# 1.net
KiCad netlist of a schematic drawn in EAGLE
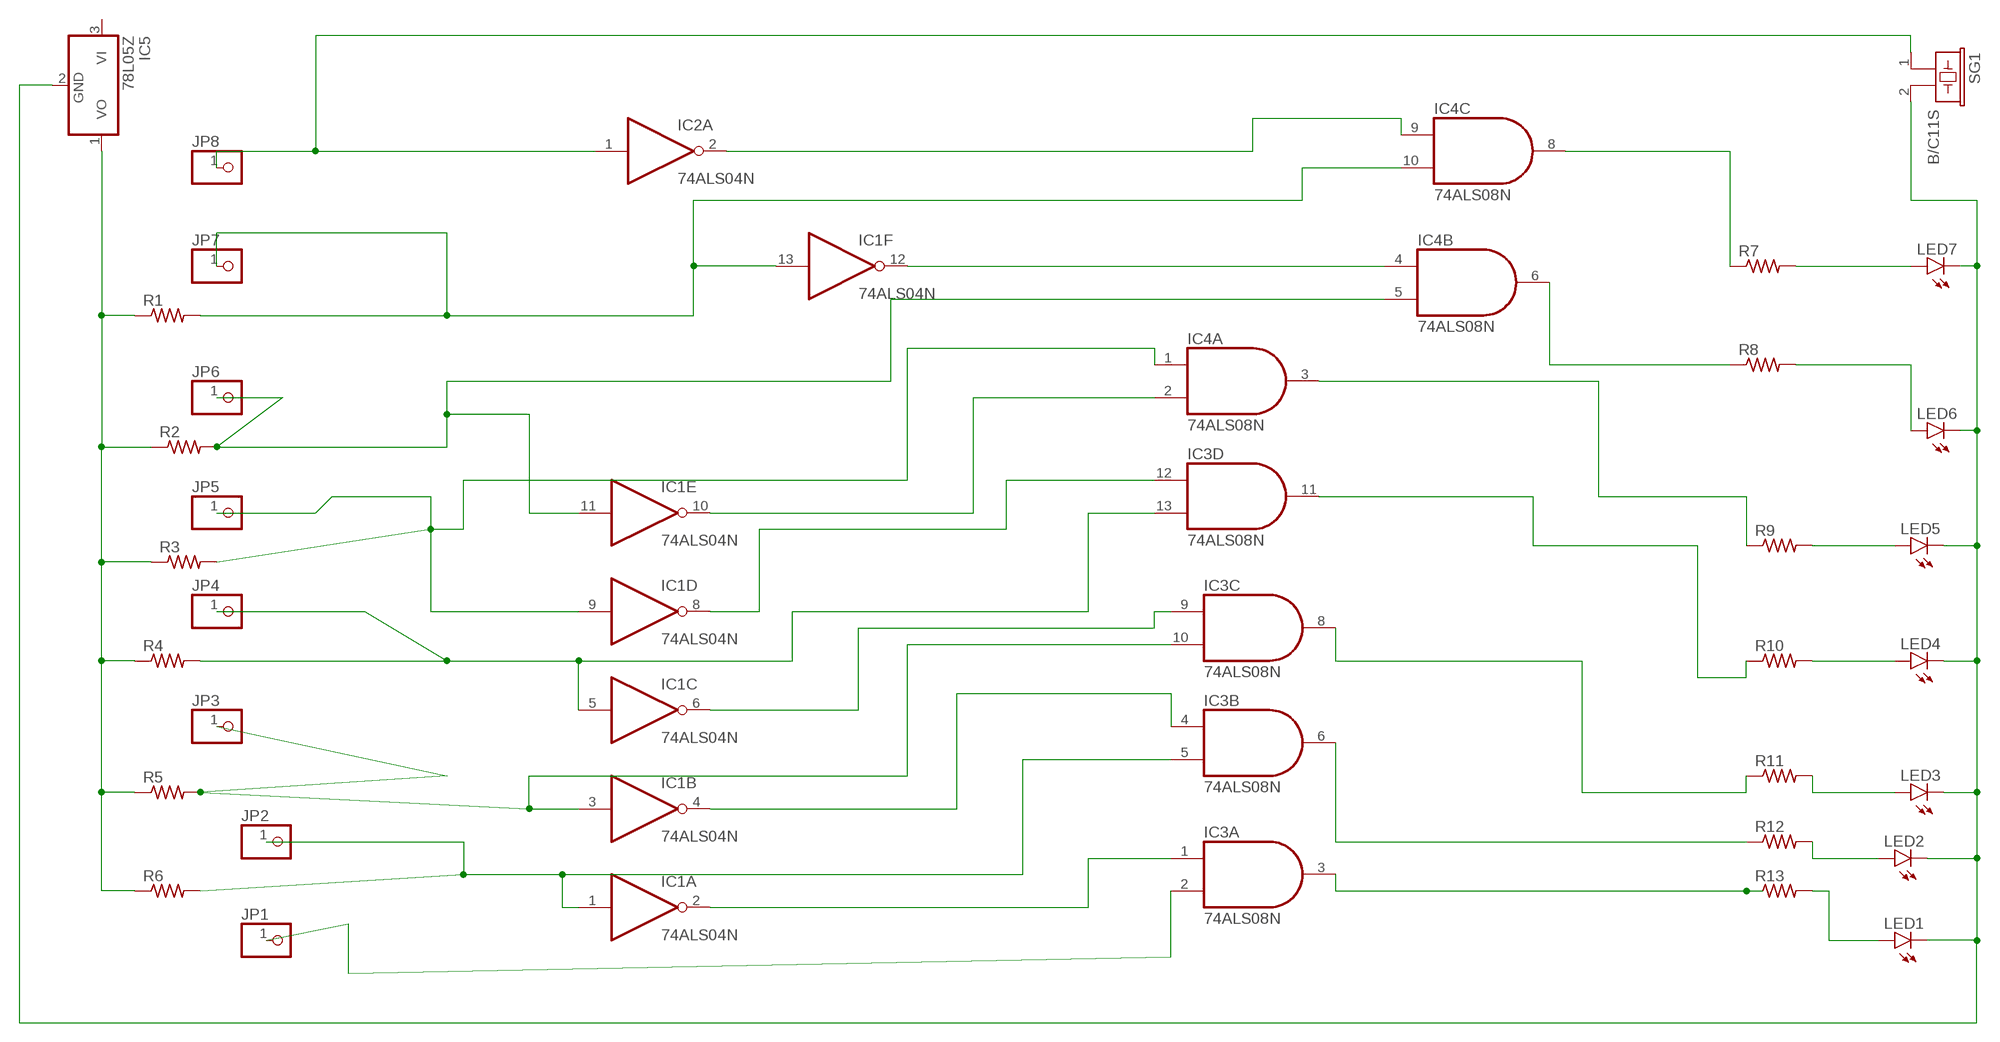
[diagram p0: schematic, sheet 1]

(export (version "E")
  (design (tool "Eeschema 10.0.6"))
  (components
    (comp (ref "IC1")
      (value "74ALS04N")
      (footprint "eagle-import:DIL14")
      (libsource (lib "eagle-import") (part "7404NALS"))
    )
    (comp (ref "IC2")
      (value "74ALS04N")
      (footprint "eagle-import:DIL14")
      (libsource (lib "eagle-import") (part "7404NALS"))
    )
    (comp (ref "IC3")
      (value "74ALS08N")
      (footprint "eagle-import:DIL14")
      (libsource (lib "eagle-import") (part "7408NALS"))
    )
    (comp (ref "IC4")
      (value "74ALS08N")
      (footprint "eagle-import:DIL14")
      (libsource (lib "eagle-import") (part "7408NALS"))
    )
    (comp (ref "IC5")
      (value "78L05Z")
      (footprint "eagle-import:TO92")
      (libsource (lib "eagle-import") (part "78ZL05"))
    )
    (comp (ref "JP1")
      (value "PINHD-1X1")
      (footprint "eagle-import:1X01")
      (libsource (lib "eagle-import") (part "PINHD-1X1"))
    )
    (comp (ref "JP2")
      (value "PINHD-1X1")
      (footprint "eagle-import:1X01")
      (libsource (lib "eagle-import") (part "PINHD-1X1"))
    )
    (comp (ref "JP3")
      (value "PINHD-1X1")
      (footprint "eagle-import:1X01")
      (libsource (lib "eagle-import") (part "PINHD-1X1"))
    )
    (comp (ref "JP4")
      (value "PINHD-1X1")
      (footprint "eagle-import:1X01")
      (libsource (lib "eagle-import") (part "PINHD-1X1"))
    )
    (comp (ref "JP5")
      (value "PINHD-1X1")
      (footprint "eagle-import:1X01")
      (libsource (lib "eagle-import") (part "PINHD-1X1"))
    )
    (comp (ref "JP6")
      (value "PINHD-1X1")
      (footprint "eagle-import:1X01")
      (libsource (lib "eagle-import") (part "PINHD-1X1"))
    )
    (comp (ref "JP7")
      (value "PINHD-1X1")
      (footprint "eagle-import:1X01")
      (libsource (lib "eagle-import") (part "PINHD-1X1"))
    )
    (comp (ref "JP8")
      (value "PINHD-1X1")
      (footprint "eagle-import:1X01")
      (libsource (lib "eagle-import") (part "PINHD-1X1"))
    )
    (comp (ref "LED1")
      (value "LED10MM")
      (footprint "eagle-import:LED10MM")
      (libsource (lib "eagle-import") (part "LED10MM"))
    )
    (comp (ref "LED2")
      (value "LED10MM")
      (footprint "eagle-import:LED10MM")
      (libsource (lib "eagle-import") (part "LED10MM"))
    )
    (comp (ref "LED3")
      (value "LED10MM")
      (footprint "eagle-import:LED10MM")
      (libsource (lib "eagle-import") (part "LED10MM"))
    )
    (comp (ref "LED4")
      (value "LED10MM")
      (footprint "eagle-import:LED10MM")
      (libsource (lib "eagle-import") (part "LED10MM"))
    )
    (comp (ref "LED5")
      (value "LED10MM")
      (footprint "eagle-import:LED10MM")
      (libsource (lib "eagle-import") (part "LED10MM"))
    )
    (comp (ref "LED6")
      (value "LED10MM")
      (footprint "eagle-import:LED10MM")
      (libsource (lib "eagle-import") (part "LED10MM"))
    )
    (comp (ref "LED7")
      (value "LED10MM")
      (footprint "eagle-import:LED10MM")
      (libsource (lib "eagle-import") (part "LED10MM"))
    )
    (comp (ref "R1")
      (value "R-US_0204/5")
      (footprint "eagle-import:0204_5")
      (libsource (lib "eagle-import") (part "R-US_0204/5"))
    )
    (comp (ref "R2")
      (value "R-US_0204/5")
      (footprint "eagle-import:0204_5")
      (libsource (lib "eagle-import") (part "R-US_0204/5"))
    )
    (comp (ref "R3")
      (value "R-US_0204/5")
      (footprint "eagle-import:0204_5")
      (libsource (lib "eagle-import") (part "R-US_0204/5"))
    )
    (comp (ref "R4")
      (value "R-US_0204/5")
      (footprint "eagle-import:0204_5")
      (libsource (lib "eagle-import") (part "R-US_0204/5"))
    )
    (comp (ref "R5")
      (value "R-US_0204/5")
      (footprint "eagle-import:0204_5")
      (libsource (lib "eagle-import") (part "R-US_0204/5"))
    )
    (comp (ref "R6")
      (value "R-US_0204/5")
      (footprint "eagle-import:0204_5")
      (libsource (lib "eagle-import") (part "R-US_0204/5"))
    )
    (comp (ref "R7")
      (value "R-US_0204/5")
      (footprint "eagle-import:0204_5")
      (libsource (lib "eagle-import") (part "R-US_0204/5"))
    )
    (comp (ref "R8")
      (value "R-US_0204/5")
      (footprint "eagle-import:0204_5")
      (libsource (lib "eagle-import") (part "R-US_0204/5"))
    )
    (comp (ref "R9")
      (value "R-US_0204/5")
      (footprint "eagle-import:0204_5")
      (libsource (lib "eagle-import") (part "R-US_0204/5"))
    )
    (comp (ref "R10")
      (value "R-US_0204/5")
      (footprint "eagle-import:0204_5")
      (libsource (lib "eagle-import") (part "R-US_0204/5"))
    )
    (comp (ref "R11")
      (value "R-US_0204/5")
      (footprint "eagle-import:0204_5")
      (libsource (lib "eagle-import") (part "R-US_0204/5"))
    )
    (comp (ref "R12")
      (value "R-US_0204/5")
      (footprint "eagle-import:0204_5")
      (libsource (lib "eagle-import") (part "R-US_0204/5"))
    )
    (comp (ref "R13")
      (value "R-US_0204/5")
      (footprint "eagle-import:0204_5")
      (libsource (lib "eagle-import") (part "R-US_0204/5"))
    )
    (comp (ref "SG1")
      (value "B/C11S")
      (footprint "eagle-import:B_C11S")
      (libsource (lib "eagle-import") (part "B/C11S"))
    )
  )
  (nets
    (net (code "1") (name "Net-(IC1A-I)") (class "Default")
      (node (ref "IC1") (pin "1") (pinfunction "I_1") (pintype "input"))
      (node (ref "IC3") (pin "5") (pinfunction "I1_5") (pintype "input"))
      (node (ref "JP2") (pin "1") (pinfunction "1_1") (pintype "passive"))
      (node (ref "R6") (pin "2") (pinfunction "2_2") (pintype "passive"))
    )
    (net (code "2") (name "Net-(IC1A-O)") (class "Default")
      (node (ref "IC1") (pin "2") (pinfunction "O_2") (pintype "output"))
      (node (ref "IC3") (pin "1") (pinfunction "I0_1") (pintype "input"))
    )
    (net (code "3") (name "Net-(IC1B-I)") (class "Default")
      (node (ref "IC1") (pin "3") (pinfunction "I_3") (pintype "input"))
      (node (ref "IC3") (pin "10") (pinfunction "I1_10") (pintype "input"))
      (node (ref "JP3") (pin "1") (pinfunction "1_1") (pintype "passive"))
      (node (ref "R5") (pin "2") (pinfunction "2_2") (pintype "passive"))
    )
    (net (code "4") (name "Net-(IC1B-O)") (class "Default")
      (node (ref "IC1") (pin "4") (pinfunction "O_4") (pintype "output"))
      (node (ref "IC3") (pin "4") (pinfunction "I0_4") (pintype "input"))
    )
    (net (code "5") (name "Net-(IC1C-I)") (class "Default")
      (node (ref "IC1") (pin "5") (pinfunction "I_5") (pintype "input"))
      (node (ref "IC3") (pin "13") (pinfunction "I1_13") (pintype "input"))
      (node (ref "JP4") (pin "1") (pinfunction "1_1") (pintype "passive"))
      (node (ref "R4") (pin "2") (pinfunction "2_2") (pintype "passive"))
    )
    (net (code "6") (name "Net-(IC1C-O)") (class "Default")
      (node (ref "IC1") (pin "6") (pinfunction "O_6") (pintype "output"))
      (node (ref "IC3") (pin "9") (pinfunction "I0_9") (pintype "input"))
    )
    (net (code "7") (name "Net-(IC1D-I)") (class "Default")
      (node (ref "IC1") (pin "9") (pinfunction "I_9") (pintype "input"))
      (node (ref "IC4") (pin "1") (pinfunction "I0_1") (pintype "input"))
      (node (ref "JP5") (pin "1") (pinfunction "1_1") (pintype "passive"))
      (node (ref "R3") (pin "2") (pinfunction "2_2") (pintype "passive"))
    )
    (net (code "8") (name "Net-(IC1D-O)") (class "Default")
      (node (ref "IC1") (pin "8") (pinfunction "O_8") (pintype "output"))
      (node (ref "IC3") (pin "12") (pinfunction "I0_12") (pintype "input"))
    )
    (net (code "9") (name "Net-(IC1E-I)") (class "Default")
      (node (ref "IC1") (pin "11") (pinfunction "I_11") (pintype "input"))
      (node (ref "IC4") (pin "5") (pinfunction "I1_5") (pintype "input"))
      (node (ref "JP6") (pin "1") (pinfunction "1_1") (pintype "passive"))
      (node (ref "R2") (pin "2") (pinfunction "2_2") (pintype "passive"))
    )
    (net (code "10") (name "Net-(IC1E-O)") (class "Default")
      (node (ref "IC1") (pin "10") (pinfunction "O_10") (pintype "output"))
      (node (ref "IC4") (pin "2") (pinfunction "I1_2") (pintype "input"))
    )
    (net (code "11") (name "Net-(IC1F-I)") (class "Default")
      (node (ref "IC1") (pin "13") (pinfunction "I_13") (pintype "input"))
      (node (ref "IC4") (pin "10") (pinfunction "I1_10") (pintype "input"))
      (node (ref "JP7") (pin "1") (pinfunction "1_1") (pintype "passive"))
      (node (ref "R1") (pin "2") (pinfunction "2_2") (pintype "passive"))
    )
    (net (code "12") (name "Net-(IC1F-O)") (class "Default")
      (node (ref "IC1") (pin "12") (pinfunction "O_12") (pintype "output"))
      (node (ref "IC4") (pin "4") (pinfunction "I0_4") (pintype "input"))
    )
    (net (code "13") (name "Net-(IC2A-I)") (class "Default")
      (node (ref "IC2") (pin "1") (pinfunction "I_1") (pintype "input"))
      (node (ref "JP8") (pin "1") (pinfunction "1_1") (pintype "passive"))
      (node (ref "SG1") (pin "1") (pinfunction "1_1") (pintype "passive"))
    )
    (net (code "14") (name "Net-(IC2A-O)") (class "Default")
      (node (ref "IC2") (pin "2") (pinfunction "O_2") (pintype "output"))
      (node (ref "IC4") (pin "9") (pinfunction "I0_9") (pintype "input"))
    )
    (net (code "15") (name "Net-(IC3A-I1)") (class "Default")
      (node (ref "IC3") (pin "2") (pinfunction "I1_2") (pintype "input"))
      (node (ref "JP1") (pin "1") (pinfunction "1_1") (pintype "passive"))
    )
    (net (code "16") (name "Net-(IC3A-O)") (class "Default")
      (node (ref "IC3") (pin "3") (pinfunction "O_3") (pintype "output"))
      (node (ref "R13") (pin "1") (pinfunction "1_1") (pintype "passive"))
    )
    (net (code "17") (name "Net-(IC3B-O)") (class "Default")
      (node (ref "IC3") (pin "6") (pinfunction "O_6") (pintype "output"))
      (node (ref "R12") (pin "1") (pinfunction "1_1") (pintype "passive"))
    )
    (net (code "18") (name "Net-(IC3C-O)") (class "Default")
      (node (ref "IC3") (pin "8") (pinfunction "O_8") (pintype "output"))
      (node (ref "R11") (pin "1") (pinfunction "1_1") (pintype "passive"))
    )
    (net (code "19") (name "Net-(IC3D-O)") (class "Default")
      (node (ref "IC3") (pin "11") (pinfunction "O_11") (pintype "output"))
      (node (ref "R10") (pin "1") (pinfunction "1_1") (pintype "passive"))
    )
    (net (code "20") (name "Net-(IC4A-O)") (class "Default")
      (node (ref "IC4") (pin "3") (pinfunction "O_3") (pintype "output"))
      (node (ref "R9") (pin "1") (pinfunction "1_1") (pintype "passive"))
    )
    (net (code "21") (name "Net-(IC4B-O)") (class "Default")
      (node (ref "IC4") (pin "6") (pinfunction "O_6") (pintype "output"))
      (node (ref "R8") (pin "1") (pinfunction "1_1") (pintype "passive"))
    )
    (net (code "22") (name "Net-(IC4C-O)") (class "Default")
      (node (ref "IC4") (pin "8") (pinfunction "O_8") (pintype "output"))
      (node (ref "R7") (pin "1") (pinfunction "1_1") (pintype "passive"))
    )
    (net (code "23") (name "Net-(IC5-GND)") (class "Default")
      (node (ref "IC5") (pin "2") (pinfunction "GND_2") (pintype "passive"))
      (node (ref "LED1") (pin "K") (pinfunction "C_K") (pintype "passive"))
      (node (ref "LED2") (pin "K") (pinfunction "C_K") (pintype "passive"))
      (node (ref "LED3") (pin "K") (pinfunction "C_K") (pintype "passive"))
      (node (ref "LED4") (pin "K") (pinfunction "C_K") (pintype "passive"))
      (node (ref "LED5") (pin "K") (pinfunction "C_K") (pintype "passive"))
      (node (ref "LED6") (pin "K") (pinfunction "C_K") (pintype "passive"))
      (node (ref "LED7") (pin "K") (pinfunction "C_K") (pintype "passive"))
      (node (ref "SG1") (pin "2") (pinfunction "2_2") (pintype "passive"))
    )
    (net (code "24") (name "Net-(IC5-VO)") (class "Default")
      (node (ref "IC5") (pin "1") (pinfunction "VO_1") (pintype "passive"))
      (node (ref "R1") (pin "1") (pinfunction "1_1") (pintype "passive"))
      (node (ref "R2") (pin "1") (pinfunction "1_1") (pintype "passive"))
      (node (ref "R3") (pin "1") (pinfunction "1_1") (pintype "passive"))
      (node (ref "R4") (pin "1") (pinfunction "1_1") (pintype "passive"))
      (node (ref "R5") (pin "1") (pinfunction "1_1") (pintype "passive"))
      (node (ref "R6") (pin "1") (pinfunction "1_1") (pintype "passive"))
    )
    (net (code "25") (name "Net-(LED1-PadA)") (class "Default")
      (node (ref "LED1") (pin "A") (pinfunction "A_A") (pintype "passive"))
      (node (ref "R13") (pin "2") (pinfunction "2_2") (pintype "passive"))
    )
    (net (code "26") (name "Net-(LED2-PadA)") (class "Default")
      (node (ref "LED2") (pin "A") (pinfunction "A_A") (pintype "passive"))
      (node (ref "R12") (pin "2") (pinfunction "2_2") (pintype "passive"))
    )
    (net (code "27") (name "Net-(LED3-PadA)") (class "Default")
      (node (ref "LED3") (pin "A") (pinfunction "A_A") (pintype "passive"))
      (node (ref "R11") (pin "2") (pinfunction "2_2") (pintype "passive"))
    )
    (net (code "28") (name "Net-(LED4-PadA)") (class "Default")
      (node (ref "LED4") (pin "A") (pinfunction "A_A") (pintype "passive"))
      (node (ref "R10") (pin "2") (pinfunction "2_2") (pintype "passive"))
    )
    (net (code "29") (name "Net-(LED5-PadA)") (class "Default")
      (node (ref "LED5") (pin "A") (pinfunction "A_A") (pintype "passive"))
      (node (ref "R9") (pin "2") (pinfunction "2_2") (pintype "passive"))
    )
    (net (code "30") (name "Net-(LED6-PadA)") (class "Default")
      (node (ref "LED6") (pin "A") (pinfunction "A_A") (pintype "passive"))
      (node (ref "R8") (pin "2") (pinfunction "2_2") (pintype "passive"))
    )
    (net (code "31") (name "Net-(LED7-PadA)") (class "Default")
      (node (ref "LED7") (pin "A") (pinfunction "A_A") (pintype "passive"))
      (node (ref "R7") (pin "2") (pinfunction "2_2") (pintype "passive"))
    )
    (net (code "32") (name "unconnected-(IC5-VI-Pad3)") (class "Default")
      (node (ref "IC5") (pin "3") (pinfunction "VI_3") (pintype "input"))
    )
  )
)
